# EVK_External_Connector.net
KiCad netlist of a schematic drawn in Altium Designer
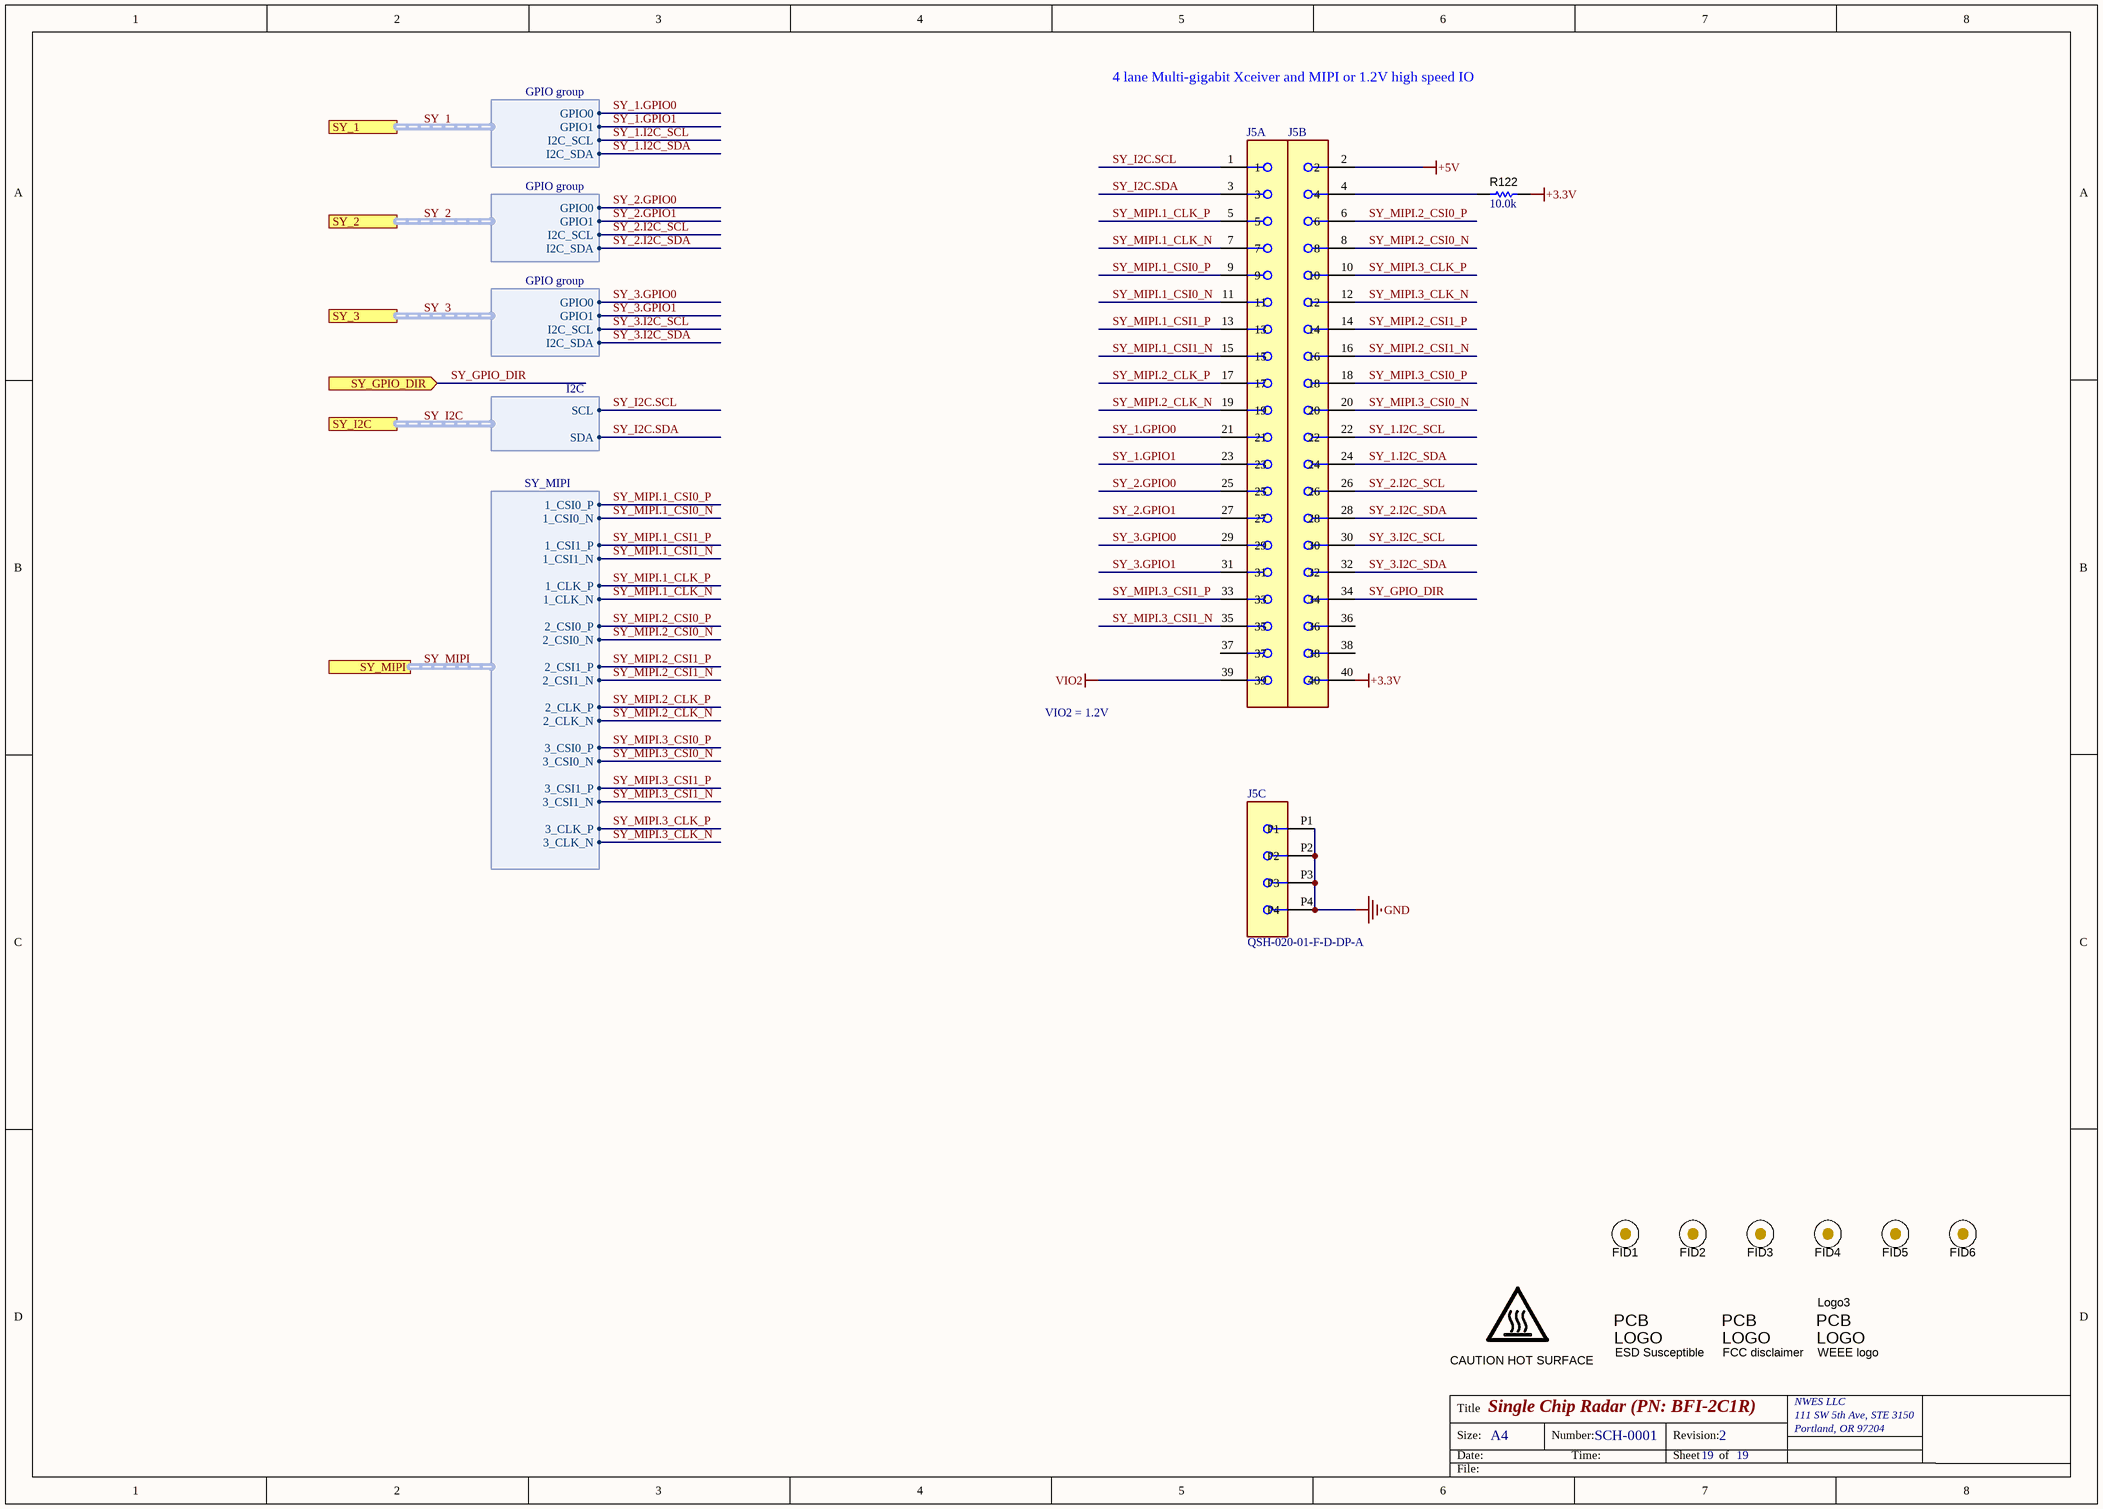
[diagram p0: EVK External Connector.SchDoc]

(export (version "E")
  (design (tool "Eeschema 10.0.6"))
  (components
    (comp (ref "ESD Susceptible1")
      (value "ESD Susceptible")
      (footprint "ESD_Overlay_Small")
      (description "ESD Susceptible Symbol")
      (fields (field (name "PUBLISHER") "Texas Instruments") (field (name "SYMBOLCREATOR") "a0412235"))
      (libsource (lib "Radar FPGA RF") (part "CMP-0074840-1"))
    )
    (comp (ref "FID1")
      (value "Fiducial")
      (footprint "Fiducial10-20")
      (description "Fiducial mark.  There is nothing to buy or mount.")
      (libsource (lib "Altium Vault - TI") (part "Fiducial"))
    )
    (comp (ref "FID2")
      (value "Fiducial")
      (footprint "Fiducial10-20")
      (description "Fiducial mark.  There is nothing to buy or mount.")
      (libsource (lib "Altium Vault - TI") (part "CMP-0077181-1"))
    )
    (comp (ref "FID3")
      (value "Fiducial")
      (footprint "Fiducial10-20")
      (description "Fiducial mark.  There is nothing to buy or mount.")
      (libsource (lib "Altium Vault - TI") (part "CMP-0077181-1"))
    )
    (comp (ref "FID4")
      (value "Fiducial")
      (footprint "Fiducial10-20")
      (description "Fiducial mark.  There is nothing to buy or mount.")
      (libsource (lib "Altium Vault - TI") (part "Fiducial"))
    )
    (comp (ref "FID5")
      (value "Fiducial")
      (footprint "Fiducial10-20")
      (description "Fiducial mark.  There is nothing to buy or mount.")
      (libsource (lib "Altium Vault - TI") (part "CMP-0077181-1"))
    )
    (comp (ref "FID6")
      (value "Fiducial")
      (footprint "Fiducial10-20")
      (description "Fiducial mark.  There is nothing to buy or mount.")
      (libsource (lib "Altium Vault - TI") (part "Fiducial"))
    )
    (comp (ref "J5")
      (value "QSH-020-01-F-D-DP-A")
      (footprint "FP-QSH-020-01-F-D-DP-A-MFG")
      (description "CONN DIFF ARRAY RCP 40P SMD GOLD")
      (fields (field (name "MANUFACTURER") "Samtec"))
      (libsource (lib "Altium Content Vault") (part "c730fc25a0432948e6f85bcb3edafa5"))
    )
    (comp (ref "Logo2")
      (value "FCC disclaimer")
      (footprint "FCC_disclaimer")
      (description "FCC_disclaimer")
      (fields (field (name "PUBLISHER") "Texas Instruments"))
      (libsource (lib "Radar FPGA RF") (part "CMP-0074847-1"))
    )
    (comp (ref "Logo3")
      (value "WEEE logo")
      (footprint "WEEE_Minimum")
      (libsource (lib "Radar FPGA RF") (part "Logo"))
    )
    (comp (ref "LOGO4")
      (value "CAUTION HOT SURFACE")
      (footprint "IEC_HotSurface_Small")
      (description "IEC 61010-1 Hot Surface Warning")
      (fields (field (name "PUBLISHER") "Texas Instruments") (field (name "SYMBOLCREATOR") "a0412235"))
      (libsource (lib "Radar FPGA RF") (part "CMP-0074837-1"))
    )
    (comp (ref "R122")
      (value "CRCW040210K0FKED")
      (footprint "0402L")
      (description "RES, 10.0 k, 1%, 0.063 W, AEC-Q200 Grade 0, 0402")
      (fields (field (name "MANUFACTURER") "Vishay-Dale") (field (name "VALUEDISPLAYED") "10.0k"))
      (libsource (lib "Radar FPGA RF") (part "Resistor"))
    )
  )
  (nets
    (net (code "9") (name "+3.3V") (class "Default")
      (node (ref "J5") (pin "40") (pinfunction "40_40") (pintype "passive"))
      (node (ref "R122") (pin "1") (pinfunction "1_1") (pintype "passive"))
    )
    (net (code "10") (name "+5V") (class "Default")
      (node (ref "J5") (pin "2") (pinfunction "2_2") (pintype "passive"))
    )
    (net (code "11") (name "/SY_1.GPIO0") (class "Default")
      (node (ref "J5") (pin "21") (pinfunction "21_21") (pintype "passive"))
    )
    (net (code "12") (name "/SY_1.GPIO1") (class "Default")
      (node (ref "J5") (pin "23") (pinfunction "23_23") (pintype "passive"))
    )
    (net (code "13") (name "/SY_1.I2C_SCL") (class "Default")
      (node (ref "J5") (pin "22") (pinfunction "22_22") (pintype "passive"))
    )
    (net (code "14") (name "/SY_1.I2C_SDA") (class "Default")
      (node (ref "J5") (pin "24") (pinfunction "24_24") (pintype "passive"))
    )
    (net (code "16") (name "/SY_2.GPIO0") (class "Default")
      (node (ref "J5") (pin "25") (pinfunction "25_25") (pintype "passive"))
    )
    (net (code "17") (name "/SY_2.GPIO1") (class "Default")
      (node (ref "J5") (pin "27") (pinfunction "27_27") (pintype "passive"))
    )
    (net (code "18") (name "/SY_2.I2C_SCL") (class "Default")
      (node (ref "J5") (pin "26") (pinfunction "26_26") (pintype "passive"))
    )
    (net (code "19") (name "/SY_2.I2C_SDA") (class "Default")
      (node (ref "J5") (pin "28") (pinfunction "28_28") (pintype "passive"))
    )
    (net (code "21") (name "/SY_3.GPIO0") (class "Default")
      (node (ref "J5") (pin "29") (pinfunction "29_29") (pintype "passive"))
    )
    (net (code "22") (name "/SY_3.GPIO1") (class "Default")
      (node (ref "J5") (pin "31") (pinfunction "31_31") (pintype "passive"))
    )
    (net (code "23") (name "/SY_3.I2C_SCL") (class "Default")
      (node (ref "J5") (pin "30") (pinfunction "30_30") (pintype "passive"))
    )
    (net (code "24") (name "/SY_3.I2C_SDA") (class "Default")
      (node (ref "J5") (pin "32") (pinfunction "32_32") (pintype "passive"))
    )
    (net (code "26") (name "/SY_GPIO_DIR") (class "Default")
      (node (ref "J5") (pin "34") (pinfunction "34_34") (pintype "passive"))
    )
    (net (code "27") (name "/SY_I2C.SCL") (class "Default")
      (node (ref "J5") (pin "1") (pinfunction "1_1") (pintype "passive"))
    )
    (net (code "28") (name "/SY_I2C.SDA") (class "Default")
      (node (ref "J5") (pin "3") (pinfunction "3_3") (pintype "passive"))
    )
    (net (code "30") (name "/SY_MIPI.1_CLK_N") (class "Default")
      (node (ref "J5") (pin "7") (pinfunction "7_7") (pintype "passive"))
    )
    (net (code "31") (name "/SY_MIPI.1_CLK_P") (class "Default")
      (node (ref "J5") (pin "5") (pinfunction "5_5") (pintype "passive"))
    )
    (net (code "32") (name "/SY_MIPI.1_CSI0_N") (class "Default")
      (node (ref "J5") (pin "11") (pinfunction "11_11") (pintype "passive"))
    )
    (net (code "33") (name "/SY_MIPI.1_CSI0_P") (class "Default")
      (node (ref "J5") (pin "9") (pinfunction "9_9") (pintype "passive"))
    )
    (net (code "34") (name "/SY_MIPI.1_CSI1_N") (class "Default")
      (node (ref "J5") (pin "15") (pinfunction "15_15") (pintype "passive"))
    )
    (net (code "35") (name "/SY_MIPI.1_CSI1_P") (class "Default")
      (node (ref "J5") (pin "13") (pinfunction "13_13") (pintype "passive"))
    )
    (net (code "36") (name "/SY_MIPI.2_CLK_N") (class "Default")
      (node (ref "J5") (pin "19") (pinfunction "19_19") (pintype "passive"))
    )
    (net (code "37") (name "/SY_MIPI.2_CLK_P") (class "Default")
      (node (ref "J5") (pin "17") (pinfunction "17_17") (pintype "passive"))
    )
    (net (code "38") (name "/SY_MIPI.2_CSI0_N") (class "Default")
      (node (ref "J5") (pin "8") (pinfunction "8_8") (pintype "passive"))
    )
    (net (code "39") (name "/SY_MIPI.2_CSI0_P") (class "Default")
      (node (ref "J5") (pin "6") (pinfunction "6_6") (pintype "passive"))
    )
    (net (code "40") (name "/SY_MIPI.2_CSI1_N") (class "Default")
      (node (ref "J5") (pin "16") (pinfunction "16_16") (pintype "passive"))
    )
    (net (code "41") (name "/SY_MIPI.2_CSI1_P") (class "Default")
      (node (ref "J5") (pin "14") (pinfunction "14_14") (pintype "passive"))
    )
    (net (code "42") (name "/SY_MIPI.3_CLK_N") (class "Default")
      (node (ref "J5") (pin "12") (pinfunction "12_12") (pintype "passive"))
    )
    (net (code "43") (name "/SY_MIPI.3_CLK_P") (class "Default")
      (node (ref "J5") (pin "10") (pinfunction "10_10") (pintype "passive"))
    )
    (net (code "44") (name "/SY_MIPI.3_CSI0_N") (class "Default")
      (node (ref "J5") (pin "20") (pinfunction "20_20") (pintype "passive"))
    )
    (net (code "45") (name "/SY_MIPI.3_CSI0_P") (class "Default")
      (node (ref "J5") (pin "18") (pinfunction "18_18") (pintype "passive"))
    )
    (net (code "46") (name "/SY_MIPI.3_CSI1_N") (class "Default")
      (node (ref "J5") (pin "35") (pinfunction "35_35") (pintype "passive"))
    )
    (net (code "47") (name "/SY_MIPI.3_CSI1_P") (class "Default")
      (node (ref "J5") (pin "33") (pinfunction "33_33") (pintype "passive"))
    )
    (net (code "49") (name "GND") (class "Default")
      (node (ref "J5") (pin "P1") (pinfunction "P1_P1") (pintype "power_in"))
      (node (ref "J5") (pin "P2") (pinfunction "P2_P2") (pintype "power_in"))
      (node (ref "J5") (pin "P3") (pinfunction "P3_P3") (pintype "power_in"))
      (node (ref "J5") (pin "P4") (pinfunction "P4_P4") (pintype "power_in"))
    )
    (net (code "50") (name "Net-(J5-Pad4)") (class "Default")
      (node (ref "J5") (pin "4") (pinfunction "4_4") (pintype "passive"))
      (node (ref "R122") (pin "2") (pinfunction "2_2") (pintype "passive"))
    )
    (net (code "51") (name "VIO2") (class "Default")
      (node (ref "J5") (pin "39") (pinfunction "39_39") (pintype "passive"))
    )
    (net (code "52") (name "unconnected-(J5-Pad36)") (class "Default")
      (node (ref "J5") (pin "36") (pinfunction "36_36") (pintype "passive"))
    )
    (net (code "53") (name "unconnected-(J5-Pad37)") (class "Default")
      (node (ref "J5") (pin "37") (pinfunction "37_37") (pintype "passive"))
    )
    (net (code "54") (name "unconnected-(J5-Pad38)") (class "Default")
      (node (ref "J5") (pin "38") (pinfunction "38_38") (pintype "passive"))
    )
  )
)
